# V2.net
KiCad netlist of a schematic drawn in EasyEDA Pro
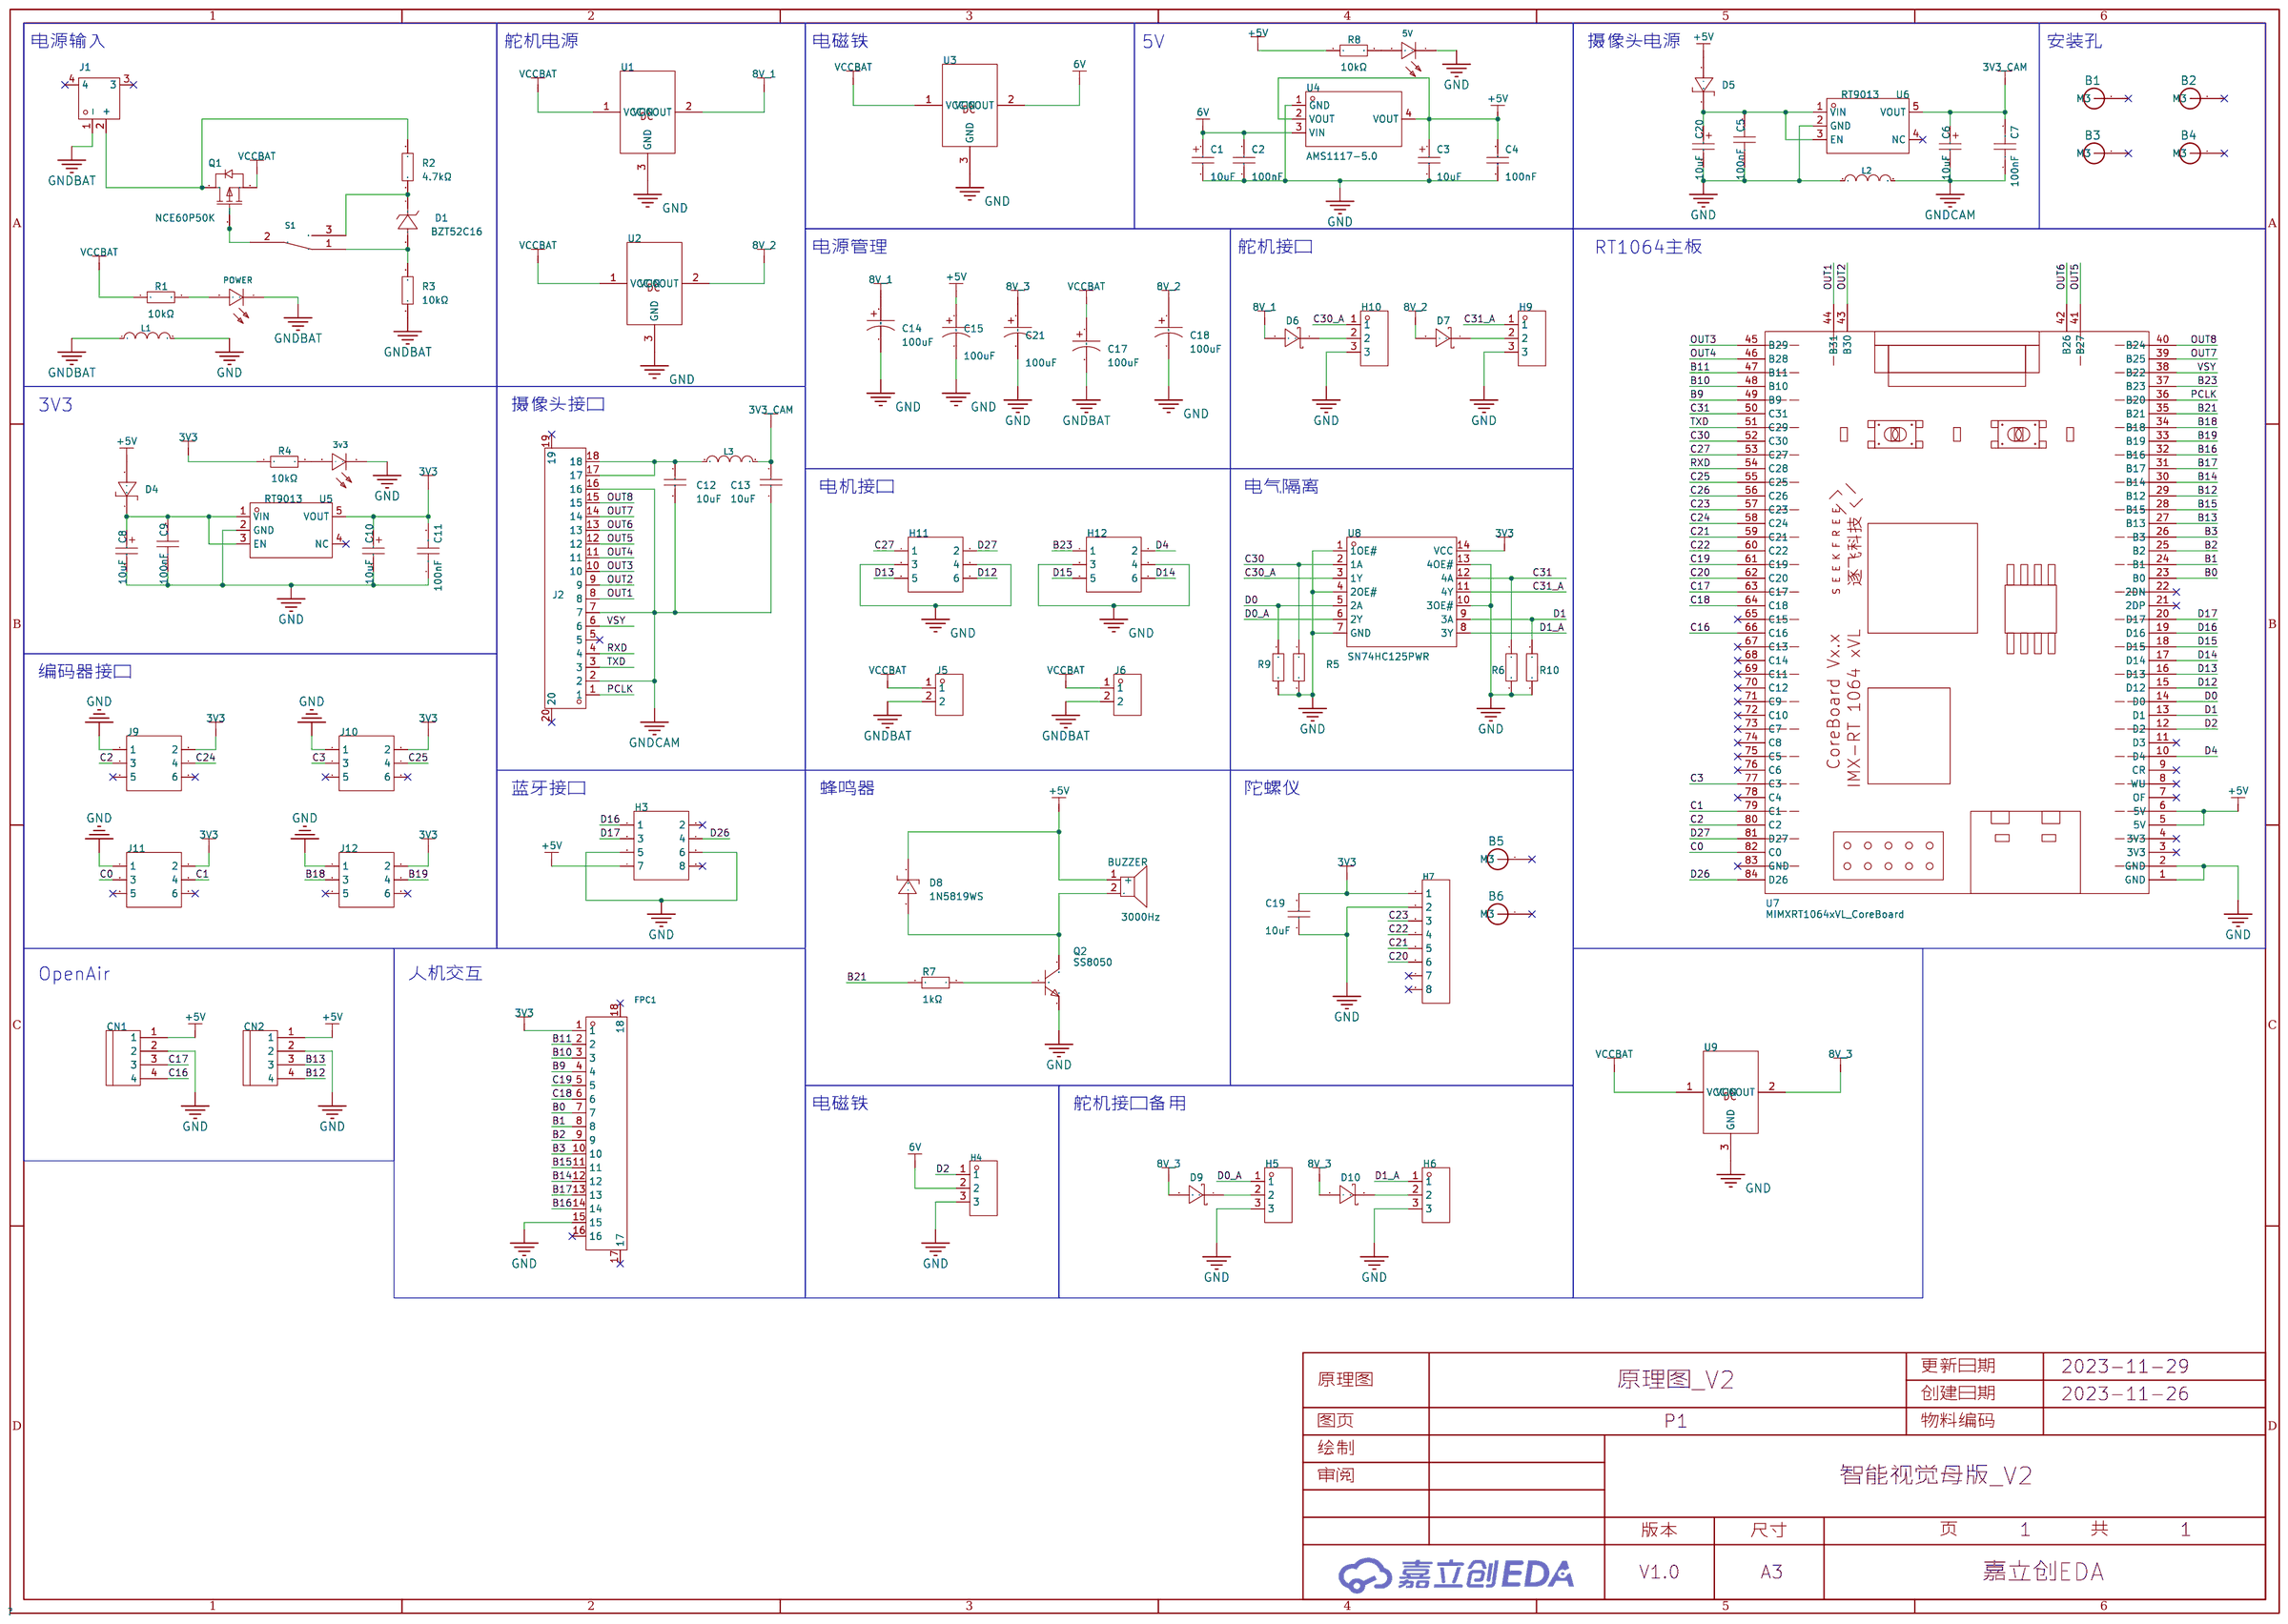
[diagram p0: schematic sheet]

(export (version "E")
  (design (tool "Eeschema 10.0.6"))
  (components
    (comp (ref "3v3")
      (value "NCD0603W1")
      (footprint "easyedapro:LED0603-RD")
      (description "发光颜色:白灯;")
      (fields (field (name "Manufacturer") "国星光电"))
      (libsource (lib "easyedapro") (part "FC-D1608WD-460H5"))
    )
    (comp (ref "5V")
      (value "NCD0603W1")
      (footprint "easyedapro:LED0603-RD")
      (description "发光颜色:白灯;")
      (fields (field (name "Manufacturer") "国星光电"))
      (libsource (lib "easyedapro") (part "FC-D1608WD-460H5"))
    )
    (comp (ref "B1")
      (value "M3螺柱孔_JX")
      (footprint "easyedapro:M3")
      (libsource (lib "easyedapro") (part "M3螺柱孔_JX"))
    )
    (comp (ref "B2")
      (value "M3螺柱孔_JX")
      (footprint "easyedapro:M3")
      (libsource (lib "easyedapro") (part "M3螺柱孔_JX"))
    )
    (comp (ref "B3")
      (value "M3螺柱孔_JX")
      (footprint "easyedapro:M3")
      (libsource (lib "easyedapro") (part "M3螺柱孔_JX"))
    )
    (comp (ref "B4")
      (value "M3螺柱孔_JX")
      (footprint "easyedapro:M3")
      (libsource (lib "easyedapro") (part "M3螺柱孔_JX"))
    )
    (comp (ref "B5")
      (value "M3螺柱孔_JX")
      (footprint "easyedapro:M3")
      (libsource (lib "easyedapro") (part "M3螺柱孔_JX"))
    )
    (comp (ref "B6")
      (value "M3螺柱孔_JX")
      (footprint "easyedapro:M3")
      (libsource (lib "easyedapro") (part "M3螺柱孔_JX"))
    )
    (comp (ref "BUZZER")
      (value "3000Hz")
      (footprint "easyedapro:BUZ-TH_BD9.6-P5.00-D0.7-FD")
      (description "驱动方式:有源(内含驱动线路);构造类型:电磁式;额定电压:5V;工作电压:4V~8V;频率:3000Hz;声压(SPL):85dB@5V,10cm;直径(φD):9mm;高度:5.7mm;")
      (fields (field (name "Manufacturer Part") "HNB09A05") (field (name "Manufacturer") "华能"))
      (libsource (lib "easyedapro") (part "HNB09A05"))
    )
    (comp (ref "C1")
      (value "10uF")
      (footprint "easyedapro:CAP-SMD_L3.2-W1.6-RD-C7171")
      (description "容值:10uF;精度:±10%;额定电压:16V;等效串联电阻:3Ω@100kHz;")
      (fields (field (name "Manufacturer Part") "TAJA106K016RNJ") (field (name "Manufacturer") "Kyocera AVX"))
      (libsource (lib "easyedapro") (part "TAJA106K016RNJ"))
    )
    (comp (ref "C2")
      (value "100nF")
      (footprint "easyedapro:C0603")
      (description "容值:100nF;精度:±10%;额定电压:50V;材质(温度系数):X7R;")
      (fields (field (name "Manufacturer Part") "0603B104K500NT") (field (name "Manufacturer") "FH(风华)"))
      (libsource (lib "easyedapro") (part "0603B104K500NT"))
    )
    (comp (ref "C3")
      (value "10uF")
      (footprint "easyedapro:CAP-SMD_L3.2-W1.6-RD-C7171")
      (description "容值:10uF;精度:±10%;额定电压:16V;等效串联电阻:3Ω@100kHz;")
      (fields (field (name "Manufacturer Part") "TAJA106K016RNJ") (field (name "Manufacturer") "Kyocera AVX"))
      (libsource (lib "easyedapro") (part "TAJA106K016RNJ"))
    )
    (comp (ref "C4")
      (value "100nF")
      (footprint "easyedapro:C0603")
      (description "容值:100nF;精度:±10%;额定电压:50V;材质(温度系数):X7R;")
      (fields (field (name "Manufacturer Part") "0603B104K500NT") (field (name "Manufacturer") "FH(风华)"))
      (libsource (lib "easyedapro") (part "0603B104K500NT"))
    )
    (comp (ref "C5")
      (value "100nF")
      (footprint "easyedapro:C0603")
      (libsource (lib "easyedapro") (part "C1210X7R475K630NT"))
    )
    (comp (ref "C6")
      (value "10uF")
      (footprint "easyedapro:CASE-A_3216")
      (description "容值:10uF;精度:±20%;额定电压:10V;等效串联电阻:8Ω@100kHz;工作温度:-55~+125;")
      (fields
        (field (name "Manufacturer Part") "CA45-A-10V-10uF-M")
        (field (name "Manufacturer") "CEC(振华新云)")
      )
      (libsource (lib "easyedapro") (part "CA45-A-10V-10UF-M"))
    )
    (comp (ref "C7")
      (value "100nF")
      (footprint "easyedapro:C0603")
      (libsource (lib "easyedapro") (part "C1210X7R475K630NT"))
    )
    (comp (ref "C8")
      (value "10uF")
      (footprint "easyedapro:CASE-A_3216")
      (description "容值:10uF;精度:±20%;额定电压:10V;等效串联电阻:8Ω@100kHz;工作温度:-55~+125;")
      (fields
        (field (name "Manufacturer Part") "CA45-A-10V-10uF-M")
        (field (name "Manufacturer") "CEC(振华新云)")
      )
      (libsource (lib "easyedapro") (part "CA45-A-10V-10UF-M"))
    )
    (comp (ref "C9")
      (value "100nF")
      (footprint "easyedapro:C0603")
      (libsource (lib "easyedapro") (part "C1210X7R475K630NT"))
    )
    (comp (ref "C10")
      (value "10uF")
      (footprint "easyedapro:CASE-A_3216")
      (description "容值:10uF;精度:±20%;额定电压:10V;等效串联电阻:8Ω@100kHz;工作温度:-55~+125;")
      (fields
        (field (name "Manufacturer Part") "CA45-A-10V-10uF-M")
        (field (name "Manufacturer") "CEC(振华新云)")
      )
      (libsource (lib "easyedapro") (part "CA45-A-10V-10UF-M"))
    )
    (comp (ref "C11")
      (value "100nF")
      (footprint "easyedapro:C0603")
      (libsource (lib "easyedapro") (part "C1210X7R475K630NT"))
    )
    (comp (ref "C12")
      (value "10uF")
      (footprint "easyedapro:C0805")
      (description "容值:10uF;精度:±10%;额定电压:25V;材质(温度系数):X5R;")
      (fields
        (field (name "Manufacturer Part") "CL21A106KAYNNNE")
        (field (name "Manufacturer") "SAMSUNG(三星)")
      )
      (libsource (lib "easyedapro") (part "CL21A106KAYNNNE"))
    )
    (comp (ref "C13")
      (value "10uF")
      (footprint "easyedapro:C0805")
      (description "容值:10uF;精度:±10%;额定电压:25V;材质(温度系数):X5R;")
      (fields
        (field (name "Manufacturer Part") "CL21A106KAYNNNE")
        (field (name "Manufacturer") "SAMSUNG(三星)")
      )
      (libsource (lib "easyedapro") (part "CL21A106KAYNNNE"))
    )
    (comp (ref "C14")
      (value "100uF")
      (footprint "easyedapro:CAP-TH_BD8.0-P3.50-D0.6-FD")
      (fields
        (field (name "Manufacturer Part") "25PZE220M8X9")
        (field (name "Manufacturer") "rubycon(红宝石)")
        (field (name "Tolerance") "±20%")
      )
      (libsource (lib "easyedapro") (part "25PZE220M8X9"))
    )
    (comp (ref "C15")
      (value "100uF")
      (footprint "easyedapro:CAP-TH_BD8.0-P3.50-D0.6-FD")
      (fields
        (field (name "Manufacturer Part") "25PZE220M8X9")
        (field (name "Manufacturer") "rubycon(红宝石)")
        (field (name "Tolerance") "±20%")
      )
      (libsource (lib "easyedapro") (part "25PZE220M8X9"))
    )
    (comp (ref "C17")
      (value "100uF")
      (footprint "easyedapro:CAP-TH_BD8.0-P3.50-D0.6-FD")
      (fields
        (field (name "Manufacturer Part") "25PZE220M8X9")
        (field (name "Manufacturer") "rubycon(红宝石)")
        (field (name "Tolerance") "±20%")
      )
      (libsource (lib "easyedapro") (part "25PZE220M8X9"))
    )
    (comp (ref "C18")
      (value "100uF")
      (footprint "easyedapro:CAP-TH_BD8.0-P3.50-D0.6-FD")
      (fields
        (field (name "Manufacturer Part") "25PZE220M8X9")
        (field (name "Manufacturer") "rubycon(红宝石)")
        (field (name "Tolerance") "±20%")
      )
      (libsource (lib "easyedapro") (part "25PZE220M8X9"))
    )
    (comp (ref "C19")
      (value "10uF")
      (footprint "easyedapro:C0805")
      (description "容值:10uF;精度:±10%;额定电压:25V;材质(温度系数):X5R;")
      (fields
        (field (name "Manufacturer Part") "CL21A106KAYNNNE")
        (field (name "Manufacturer") "SAMSUNG(三星)")
      )
      (libsource (lib "easyedapro") (part "CL21A106KAYNNNE"))
    )
    (comp (ref "C20")
      (value "10uF")
      (footprint "easyedapro:CASE-A_3216")
      (description "容值:10uF;精度:±20%;额定电压:10V;等效串联电阻:8Ω@100kHz;工作温度:-55~+125;")
      (fields
        (field (name "Manufacturer Part") "CA45-A-10V-10uF-M")
        (field (name "Manufacturer") "CEC(振华新云)")
      )
      (libsource (lib "easyedapro") (part "CA45-A-10V-10UF-M"))
    )
    (comp (ref "C21")
      (value "100uF")
      (footprint "easyedapro:CAP-TH_BD8.0-P3.50-D0.6-FD")
      (fields
        (field (name "Manufacturer Part") "25PZE220M8X9")
        (field (name "Manufacturer") "rubycon(红宝石)")
        (field (name "Tolerance") "±20%")
      )
      (libsource (lib "easyedapro") (part "25PZE220M8X9"))
    )
    (comp (ref "CN1")
      (value "XH-4AW")
      (footprint "easyedapro:CONN-TH_XH2.54-4AW")
      (description "参考系列:XH;间距:2.5mm;插针结构:1x4P;排数:1;每排PIN数:4;行距:-;安装方式:-;触头材质:磷青铜;")
      (fields (field (name "Manufacturer") "BOOMELE(博穆精密)"))
      (libsource (lib "easyedapro") (part "XH2.54-4AW"))
    )
    (comp (ref "CN2")
      (value "XH-4AW")
      (footprint "easyedapro:CONN-TH_XH2.54-4AW")
      (description "参考系列:XH;间距:2.5mm;插针结构:1x4P;排数:1;每排PIN数:4;行距:-;安装方式:-;触头材质:磷青铜;")
      (fields (field (name "Manufacturer") "BOOMELE(博穆精密)"))
      (libsource (lib "easyedapro") (part "XH2.54-4AW"))
    )
    (comp (ref "D1")
      (value "BZT52C16")
      (footprint "easyedapro:SOD-123_L2.7-W1.6-LS3.7-RD")
      (description "稳压值(标称值):-;精度:-;功率:500mW;反向电流(Ir):100nA@11.2V;")
      (fields (field (name "Manufacturer") "Slkor(萨科微)"))
      (libsource (lib "easyedapro") (part "BZT52C16_C707145"))
    )
    (comp (ref "D4")
      (value "1N5819WS")
      (footprint "easyedapro:SOD-323_L1.8-W1.3-LS2.5-RD")
      (description "直流反向耐压(Vr):40V;平均整流电流(Io):1A;正向压降(Vf):600mV@1A;")
      (fields (field (name "Manufacturer") "Hottech(合科泰)"))
      (libsource (lib "easyedapro") (part "1N5819WS"))
    )
    (comp (ref "D5")
      (value "1N5819WS")
      (footprint "easyedapro:SOD-323_L1.8-W1.3-LS2.5-RD")
      (description "直流反向耐压(Vr):40V;平均整流电流(Io):1A;正向压降(Vf):600mV@1A;")
      (fields (field (name "Manufacturer") "Hottech(合科泰)"))
      (libsource (lib "easyedapro") (part "1N5819WS"))
    )
    (comp (ref "D6")
      (value "1N5819W")
      (footprint "easyedapro:SOD-123_L2.8-W1.8-LS3.7-RD")
      (description "正向压降(Vf):600mV@1A;直流反向耐压(Vr):40V;平均整流电流(Io):1A;")
      (fields (field (name "Manufacturer") "KEXIN(科信)"))
      (libsource (lib "easyedapro") (part "1N5819W_C369930"))
    )
    (comp (ref "D7")
      (value "1N5819W")
      (footprint "easyedapro:SOD-123_L2.8-W1.8-LS3.7-RD")
      (description "正向压降(Vf):600mV@1A;直流反向耐压(Vr):40V;平均整流电流(Io):1A;")
      (fields (field (name "Manufacturer") "KEXIN(科信)"))
      (libsource (lib "easyedapro") (part "1N5819W_C369930"))
    )
    (comp (ref "D8")
      (value "1N5819WS")
      (footprint "easyedapro:SOD-323_L1.8-W1.3-LS2.5-RD")
      (description "直流反向耐压(Vr):40V;平均整流电流(Io):1A;正向压降(Vf):600mV@1A;")
      (fields (field (name "Manufacturer") "Hottech(合科泰)"))
      (libsource (lib "easyedapro") (part "1N5819WS"))
    )
    (comp (ref "D9")
      (value "1N5819W")
      (footprint "easyedapro:SOD-123_L2.8-W1.8-LS3.7-RD")
      (description "正向压降(Vf):600mV@1A;直流反向耐压(Vr):40V;平均整流电流(Io):1A;")
      (fields (field (name "Manufacturer") "KEXIN(科信)"))
      (libsource (lib "easyedapro") (part "1N5819W_C369930"))
    )
    (comp (ref "D10")
      (value "1N5819W")
      (footprint "easyedapro:SOD-123_L2.8-W1.8-LS3.7-RD")
      (description "正向压降(Vf):600mV@1A;直流反向耐压(Vr):40V;平均整流电流(Io):1A;")
      (fields (field (name "Manufacturer") "KEXIN(科信)"))
      (libsource (lib "easyedapro") (part "1N5819W_C369930"))
    )
    (comp (ref "FPC1")
      (value "FPC-05F-16PH20")
      (footprint "easyedapro:FPC-SMD_16P-P0.50_FPC-05F-16PH20")
      (description "间距:0.5mm;触点数量:16P;锁定特性:翻盖式;安装类型:卧贴;触点类型:下接;工作温度范围:-25°C~+85°C;")
      (fields (field (name "Manufacturer") "XUNPU(讯普)"))
      (libsource (lib "easyedapro") (part "FPC-05F-16PH20"))
    )
    (comp (ref "H3")
      (value "~")
      (footprint "easyedapro:HDR-TH_8P-P2.54-V-F-R2-C4-S2.54-1")
      (libsource (lib "easyedapro") (part "HDR-F-2.54_2x4"))
    )
    (comp (ref "H4")
      (value "~")
      (footprint "easyedapro:HDR-TH_3P-P2.54-V-F")
      (libsource (lib "easyedapro") (part "PM254V-11-03-H85"))
    )
    (comp (ref "H5")
      (value "~")
      (footprint "easyedapro:HDR-TH_3P-P2.54-V-M")
      (libsource (lib "easyedapro") (part "PZ254V-11-03P_C2937625"))
    )
    (comp (ref "H6")
      (value "~")
      (footprint "easyedapro:HDR-TH_3P-P2.54-V-M")
      (libsource (lib "easyedapro") (part "PZ254V-11-03P_C2937625"))
    )
    (comp (ref "H7")
      (value "~")
      (footprint "easyedapro:HDR-TH_8P-P2.54-V-F-1")
      (libsource (lib "easyedapro") (part "Header-Female-2.54_1x8"))
    )
    (comp (ref "H9")
      (value "~")
      (footprint "easyedapro:HDR-TH_3P-P2.54-V-M")
      (libsource (lib "easyedapro") (part "PZ254V-11-03P_C2937625"))
    )
    (comp (ref "H10")
      (value "~")
      (footprint "easyedapro:HDR-TH_3P-P2.54-V-M")
      (libsource (lib "easyedapro") (part "PZ254V-11-03P_C2937625"))
    )
    (comp (ref "H11")
      (value "~")
      (footprint "easyedapro:HDR-TH_6P-P2.54-V-R2-C3-S2.54_A2541WV-2X3P")
      (libsource (lib "easyedapro") (part "HDR-M-2.54_2x3"))
    )
    (comp (ref "H12")
      (value "~")
      (footprint "easyedapro:HDR-TH_6P-P2.54-V-R2-C3-S2.54_A2541WV-2X3P")
      (libsource (lib "easyedapro") (part "HDR-M-2.54_2x3"))
    )
    (comp (ref "J1")
      (value "XT60PW-M")
      (footprint "easyedapro:CONN-TH_XT60PW-M")
      (description "模型锂电连接器")
      (fields (field (name "Manufacturer") "AMASS(艾迈斯)"))
      (libsource (lib "easyedapro") (part "XT60PW-M"))
    )
    (comp (ref "J2")
      (value "J2")
      (footprint "easyedapro:FPC-SMD_18P-P0.50_FPC-05F-18PH20")
      (description "间距:0.5mm;触点数量:18P;锁定特性:翻盖式;安装类型:卧贴;触点类型:下接;工作温度范围:-25°C~+85°C;")
      (fields (field (name "Manufacturer") "XUNPU(讯普)"))
      (libsource (lib "easyedapro") (part "FPC-05F-18PH20"))
    )
    (comp (ref "J5")
      (value "KF301-5.0-2P")
      (footprint "easyedapro:CONN-TH_P5.00_KF301-5.0-2P")
      (fields (field (name "Manufacturer") "KEFA(科发)"))
      (libsource (lib "easyedapro") (part "KF301-5.0-2P"))
    )
    (comp (ref "J6")
      (value "KF301-5.0-2P")
      (footprint "easyedapro:CONN-TH_P5.00_KF301-5.0-2P")
      (fields (field (name "Manufacturer") "KEFA(科发)"))
      (libsource (lib "easyedapro") (part "KF301-5.0-2P"))
    )
    (comp (ref "J9")
      (value "~")
      (footprint "easyedapro:HDR-TH_6P-P2.54-V-R2-C3-S2.54_A2541WV-2X3P")
      (libsource (lib "easyedapro") (part "HDR-M-2.54_2x3"))
    )
    (comp (ref "J10")
      (value "~")
      (footprint "easyedapro:HDR-TH_6P-P2.54-V-R2-C3-S2.54_A2541WV-2X3P")
      (libsource (lib "easyedapro") (part "HDR-M-2.54_2x3"))
    )
    (comp (ref "J11")
      (value "~")
      (footprint "easyedapro:HDR-TH_6P-P2.54-V-R2-C3-S2.54_A2541WV-2X3P")
      (libsource (lib "easyedapro") (part "HDR-M-2.54_2x3"))
    )
    (comp (ref "J12")
      (value "~")
      (footprint "easyedapro:HDR-TH_6P-P2.54-V-R2-C3-S2.54_A2541WV-2X3P")
      (libsource (lib "easyedapro") (part "HDR-M-2.54_2x3"))
    )
    (comp (ref "L1")
      (value "CBG201209U000T")
      (footprint "easyedapro:L0805")
      (description "标称阻抗@测试频率:0Ω@100MHz;直流电阻(RDC):80mΩ;")
      (fields (field (name "Manufacturer") "FH(风华)"))
      (libsource (lib "easyedapro") (part "CBG201209U000T"))
    )
    (comp (ref "L2")
      (value "CBG201209U000T")
      (footprint "easyedapro:L0805")
      (description "标称阻抗@测试频率:0Ω@100MHz;直流电阻(RDC):80mΩ;")
      (fields (field (name "Manufacturer") "FH(风华)"))
      (libsource (lib "easyedapro") (part "CBG201209U000T"))
    )
    (comp (ref "L3")
      (value "CBG201209U000T")
      (footprint "easyedapro:L0805")
      (description "标称阻抗@测试频率:0Ω@100MHz;直流电阻(RDC):80mΩ;")
      (fields (field (name "Manufacturer") "FH(风华)"))
      (libsource (lib "easyedapro") (part "CBG201209U000T"))
    )
    (comp (ref "POWER")
      (value "NCD0603R1")
      (footprint "easyedapro:LED0603-RD_RED")
      (description "发光颜色:红灯;")
      (fields (field (name "Manufacturer") "国星光电"))
      (libsource (lib "easyedapro") (part "FC-DA1608HRK-620D"))
    )
    (comp (ref "Q1")
      (value "NCE60P50K")
      (footprint "easyedapro:TO-252-2_L6.6-W6.1-P4.57-LS9.9-TL-CW")
      (fields (field (name "Manufacturer") "NCE(无锡新洁能)"))
      (libsource (lib "easyedapro") (part "NCE60P50K"))
    )
    (comp (ref "Q2")
      (value "SS8050")
      (footprint "easyedapro:SOT-23-3_L2.9-W1.3-P1.90-LS2.4-BR")
      (description "晶体管类型:NPN;集射极击穿电压(Vceo):25V;集电极电流(Ic):1.5A;功率(Pd):300mW;直流电流增益(hFE@Ic,Vce):200@100mA,1V;")
      (fields (field (name "Manufacturer") "CJ(江苏长电/长晶)"))
      (libsource (lib "easyedapro") (part "SS8050_C2150"))
    )
    (comp (ref "R1")
      (value "10kΩ")
      (footprint "easyedapro:R0603")
      (description "电阻类型:厚膜电阻;阻值:10kΩ;精度:±1%;功率:100mW;")
      (fields
        (field (name "Manufacturer Part") "0603WAF1002T5E")
        (field (name "Manufacturer") "UNI-ROYAL(厚声)")
      )
      (libsource (lib "easyedapro") (part "0603WAF1002T5E"))
    )
    (comp (ref "R2")
      (value "4.7kΩ")
      (footprint "easyedapro:R0603")
      (description "电阻类型:厚膜电阻;阻值:4.7kΩ;精度:±1%;功率:100mW;")
      (fields
        (field (name "Manufacturer Part") "0603WAF4701T5E")
        (field (name "Manufacturer") "UNI-ROYAL(厚声)")
      )
      (libsource (lib "easyedapro") (part "0603WAF4701T5E"))
    )
    (comp (ref "R3")
      (value "10kΩ")
      (footprint "easyedapro:R0603")
      (description "电阻类型:厚膜电阻;阻值:10kΩ;精度:±1%;功率:100mW;")
      (fields
        (field (name "Manufacturer Part") "0603WAF1002T5E")
        (field (name "Manufacturer") "UNI-ROYAL(厚声)")
      )
      (libsource (lib "easyedapro") (part "0603WAF1002T5E"))
    )
    (comp (ref "R4")
      (value "10kΩ")
      (footprint "easyedapro:R0603")
      (description "电阻类型:厚膜电阻;阻值:10kΩ;精度:±1%;功率:100mW;")
      (fields
        (field (name "Manufacturer Part") "0603WAF1002T5E")
        (field (name "Manufacturer") "UNI-ROYAL(厚声)")
      )
      (libsource (lib "easyedapro") (part "0603WAF1002T5E"))
    )
    (comp (ref "R5")
      (value "10kΩ")
      (footprint "easyedapro:R0603")
      (description "电阻类型:厚膜电阻;阻值:10kΩ;精度:±1%;功率:100mW;")
      (fields
        (field (name "Manufacturer Part") "0603WAF1002T5E")
        (field (name "Manufacturer") "UNI-ROYAL(厚声)")
      )
      (libsource (lib "easyedapro") (part "0603WAF1002T5E"))
    )
    (comp (ref "R6")
      (value "10kΩ")
      (footprint "easyedapro:R0603")
      (description "电阻类型:厚膜电阻;阻值:10kΩ;精度:±1%;功率:100mW;")
      (fields
        (field (name "Manufacturer Part") "0603WAF1002T5E")
        (field (name "Manufacturer") "UNI-ROYAL(厚声)")
      )
      (libsource (lib "easyedapro") (part "0603WAF1002T5E"))
    )
    (comp (ref "R7")
      (value "1kΩ")
      (footprint "easyedapro:R0603")
      (description "电阻类型:厚膜电阻;阻值:1kΩ;精度:±1%;功率:100mW;")
      (fields
        (field (name "Manufacturer Part") "0603WAF1001T5E")
        (field (name "Manufacturer") "UNI-ROYAL(厚声)")
      )
      (libsource (lib "easyedapro") (part "0603WAF1001T5E"))
    )
    (comp (ref "R8")
      (value "10kΩ")
      (footprint "easyedapro:R0603")
      (description "电阻类型:厚膜电阻;阻值:10kΩ;精度:±1%;功率:100mW;")
      (fields
        (field (name "Manufacturer Part") "0603WAF1002T5E")
        (field (name "Manufacturer") "UNI-ROYAL(厚声)")
      )
      (libsource (lib "easyedapro") (part "0603WAF1002T5E"))
    )
    (comp (ref "R9")
      (value "10kΩ")
      (footprint "easyedapro:R0603")
      (description "电阻类型:厚膜电阻;阻值:10kΩ;精度:±1%;功率:100mW;")
      (fields
        (field (name "Manufacturer Part") "0603WAF1002T5E")
        (field (name "Manufacturer") "UNI-ROYAL(厚声)")
      )
      (libsource (lib "easyedapro") (part "0603WAF1002T5E"))
    )
    (comp (ref "R10")
      (value "10kΩ")
      (footprint "easyedapro:R0603")
      (description "电阻类型:厚膜电阻;阻值:10kΩ;精度:±1%;功率:100mW;")
      (fields
        (field (name "Manufacturer Part") "0603WAF1002T5E")
        (field (name "Manufacturer") "UNI-ROYAL(厚声)")
      )
      (libsource (lib "easyedapro") (part "0603WAF1002T5E"))
    )
    (comp (ref "S1")
      (value "MT-0-102-A101-M200-RS")
      (footprint "easyedapro:SW-TH_MT-0-103-A101-M200-RS")
      (description "额定电流:5A;额定电压(AC):125V;电路结构:单刀双掷;机械寿命:-;安装方式:直插;")
      (fields (field (name "Manufacturer") "YUEN FUNG(源丰)"))
      (libsource (lib "easyedapro") (part "MT-0-102-A101-M200-RS+PJ"))
    )
    (comp (ref "U1") (value "~") (libsource (lib "easyedapro") (part "DC_Board")))
    (comp (ref "U2") (value "~") (libsource (lib "easyedapro") (part "DC_Board")))
    (comp (ref "U3") (value "~") (libsource (lib "easyedapro") (part "DC_Board")))
    (comp (ref "U4")
      (value "AMS1117-5.0")
      (footprint "easyedapro:SOT-223_L6.5-W3.5-P2.30-LS7.0-BR")
      (description "输出类型:固定;最大输入电压:12V;输出电压:5V;输出电流:1A;电源纹波抑制比(PSRR):68dB@(120Hz);输出极性:正;")
      (fields (field (name "Manufacturer") "AMS"))
      (libsource (lib "easyedapro") (part "AMS1117-5.0"))
    )
    (comp (ref "U5")
      (value "RT9013")
      (footprint "easyedapro:SOT-23-5_L2.9-W1.6-P0.95-LS2.8-BR")
      (fields (field (name "Manufacturer Part") "RT9013-30GB") (field (name "Manufacturer") "RICHTEK(台湾立锜)"))
      (libsource (lib "easyedapro") (part "RT9013-30GB"))
    )
    (comp (ref "U6")
      (value "RT9013")
      (footprint "easyedapro:SOT-23-5_L2.9-W1.6-P0.95-LS2.8-BR")
      (fields (field (name "Manufacturer Part") "RT9013-30GB") (field (name "Manufacturer") "RICHTEK(台湾立锜)"))
      (libsource (lib "easyedapro") (part "RT9013-30GB"))
    )
    (comp (ref "U7")
      (value "MIMXRT1064xVL_CoreBoard")
      (footprint "easyedapro:MIMXRT1064xVL_CoreBoard - 3D")
      (libsource (lib "easyedapro") (part "MIMXRT1064xVL_CoreBoard"))
    )
    (comp (ref "U8")
      (value "SN74HC125PWR")
      (footprint "easyedapro:TSSOP-14_L5.0-W4.4-P0.65-LS6.5-BL")
      (description "类型:缓冲器，非反相;电源电压:2V~6V;输入类型:-;输出类型:三态;低电平输出电流(IOL):7.8mA;高电平输出电流(IOH):7.8mA;工作温度:-40°C~+85°C;")
      (fields (field (name "Manufacturer") "TI(德州仪器)"))
      (libsource (lib "easyedapro") (part "SN74HC125PWR"))
    )
    (comp (ref "U9") (value "~") (libsource (lib "easyedapro") (part "DC_Board")))
  )
  (nets
    (net (code "1") (name "+5V") (class "Default")
      (node (ref "BUZZER") (pin "1") (pinfunction "+_1") (pintype "input"))
      (node (ref "C15") (pin "1") (pinfunction "1_1") (pintype "input"))
      (node (ref "C3") (pin "1") (pinfunction "1_1") (pintype "input"))
      (node (ref "C4") (pin "2") (pinfunction "2_2") (pintype "input"))
      (node (ref "CN1") (pin "1") (pinfunction "1_1") (pintype "unspecified"))
      (node (ref "CN2") (pin "1") (pinfunction "1_1") (pintype "unspecified"))
      (node (ref "D4") (pin "2") (pinfunction "A_2") (pintype "input"))
      (node (ref "D5") (pin "2") (pinfunction "A_2") (pintype "input"))
      (node (ref "D8") (pin "1") (pinfunction "C_1") (pintype "input"))
      (node (ref "H3") (pin "7") (pinfunction "7_7") (pintype "input"))
      (node (ref "R8") (pin "1") (pinfunction "1_1") (pintype "input"))
      (node (ref "U4") (pin "2") (pinfunction "VOUT_2") (pintype "unspecified"))
      (node (ref "U4") (pin "4") (pinfunction "VOUT_4") (pintype "unspecified"))
      (node (ref "U7") (pin "5") (pinfunction "5V_5") (pintype "input"))
      (node (ref "U7") (pin "6") (pinfunction "5V_6") (pintype "input"))
    )
    (net (code "2") (name "/B0") (class "Default")
      (node (ref "FPC1") (pin "7") (pinfunction "7_7") (pintype "input"))
      (node (ref "U7") (pin "23") (pinfunction "B0_23") (pintype "input"))
    )
    (net (code "3") (name "/B1") (class "Default")
      (node (ref "FPC1") (pin "8") (pinfunction "8_8") (pintype "input"))
      (node (ref "U7") (pin "24") (pinfunction "B1_24") (pintype "input"))
    )
    (net (code "4") (name "/B2") (class "Default")
      (node (ref "FPC1") (pin "9") (pinfunction "9_9") (pintype "input"))
      (node (ref "U7") (pin "25") (pinfunction "B2_25") (pintype "input"))
    )
    (net (code "5") (name "/B3") (class "Default")
      (node (ref "FPC1") (pin "10") (pinfunction "10_10") (pintype "input"))
      (node (ref "U7") (pin "26") (pinfunction "B3_26") (pintype "input"))
    )
    (net (code "6") (name "/B9") (class "Default")
      (node (ref "FPC1") (pin "4") (pinfunction "4_4") (pintype "input"))
      (node (ref "U7") (pin "49") (pinfunction "B9_49") (pintype "input"))
    )
    (net (code "7") (name "/B10") (class "Default")
      (node (ref "FPC1") (pin "3") (pinfunction "3_3") (pintype "input"))
      (node (ref "U7") (pin "48") (pinfunction "B10_48") (pintype "input"))
    )
    (net (code "8") (name "/B11") (class "Default")
      (node (ref "FPC1") (pin "2") (pinfunction "2_2") (pintype "input"))
      (node (ref "U7") (pin "47") (pinfunction "B11_47") (pintype "input"))
    )
    (net (code "9") (name "/B12") (class "Default")
      (node (ref "CN2") (pin "4") (pinfunction "4_4") (pintype "unspecified"))
      (node (ref "U7") (pin "29") (pinfunction "B12_29") (pintype "input"))
    )
    (net (code "10") (name "/B13") (class "Default")
      (node (ref "CN2") (pin "3") (pinfunction "3_3") (pintype "unspecified"))
      (node (ref "U7") (pin "27") (pinfunction "B13_27") (pintype "input"))
    )
    (net (code "11") (name "/B14") (class "Default")
      (node (ref "FPC1") (pin "12") (pinfunction "12_12") (pintype "input"))
      (node (ref "U7") (pin "30") (pinfunction "B14_30") (pintype "input"))
    )
    (net (code "12") (name "/B15") (class "Default")
      (node (ref "FPC1") (pin "11") (pinfunction "11_11") (pintype "input"))
      (node (ref "U7") (pin "28") (pinfunction "B15_28") (pintype "input"))
    )
    (net (code "13") (name "/B16") (class "Default")
      (node (ref "FPC1") (pin "14") (pinfunction "14_14") (pintype "input"))
      (node (ref "U7") (pin "32") (pinfunction "B16_32") (pintype "input"))
    )
    (net (code "14") (name "/B17") (class "Default")
      (node (ref "FPC1") (pin "13") (pinfunction "13_13") (pintype "input"))
      (node (ref "U7") (pin "31") (pinfunction "B17_31") (pintype "input"))
    )
    (net (code "15") (name "/B18") (class "Default")
      (node (ref "J12") (pin "3") (pinfunction "3_3") (pintype "input"))
      (node (ref "U7") (pin "34") (pinfunction "B18_34") (pintype "input"))
    )
    (net (code "16") (name "/B19") (class "Default")
      (node (ref "J12") (pin "4") (pinfunction "4_4") (pintype "input"))
      (node (ref "U7") (pin "33") (pinfunction "B19_33") (pintype "input"))
    )
    (net (code "17") (name "/B21") (class "Default")
      (node (ref "R7") (pin "1") (pinfunction "1_1") (pintype "input"))
      (node (ref "U7") (pin "35") (pinfunction "B21_35") (pintype "input"))
    )
    (net (code "18") (name "/B23") (class "Default")
      (node (ref "H12") (pin "1") (pinfunction "1_1") (pintype "input"))
      (node (ref "U7") (pin "37") (pinfunction "B23_37") (pintype "input"))
    )
    (net (code "19") (name "/C0") (class "Default")
      (node (ref "J11") (pin "3") (pinfunction "3_3") (pintype "input"))
      (node (ref "U7") (pin "82") (pinfunction "C0_82") (pintype "input"))
    )
    (net (code "20") (name "/C1") (class "Default")
      (node (ref "J11") (pin "4") (pinfunction "4_4") (pintype "input"))
      (node (ref "U7") (pin "79") (pinfunction "C1_79") (pintype "input"))
    )
    (net (code "21") (name "/C2") (class "Default")
      (node (ref "J9") (pin "3") (pinfunction "3_3") (pintype "input"))
      (node (ref "U7") (pin "80") (pinfunction "C2_80") (pintype "input"))
    )
    (net (code "22") (name "/C3") (class "Default")
      (node (ref "J10") (pin "3") (pinfunction "3_3") (pintype "input"))
      (node (ref "U7") (pin "77") (pinfunction "C3_77") (pintype "input"))
    )
    (net (code "23") (name "/C16") (class "Default")
      (node (ref "CN1") (pin "4") (pinfunction "4_4") (pintype "unspecified"))
      (node (ref "U7") (pin "66") (pinfunction "C16_66") (pintype "input"))
    )
    (net (code "24") (name "/C17") (class "Default")
      (node (ref "CN1") (pin "3") (pinfunction "3_3") (pintype "unspecified"))
      (node (ref "U7") (pin "63") (pinfunction "C17_63") (pintype "input"))
    )
    (net (code "25") (name "/C18") (class "Default")
      (node (ref "FPC1") (pin "6") (pinfunction "6_6") (pintype "input"))
      (node (ref "U7") (pin "64") (pinfunction "C18_64") (pintype "input"))
    )
    (net (code "26") (name "/C19") (class "Default")
      (node (ref "FPC1") (pin "5") (pinfunction "5_5") (pintype "input"))
      (node (ref "U7") (pin "61") (pinfunction "C19_61") (pintype "input"))
    )
    (net (code "27") (name "/C20") (class "Default")
      (node (ref "H7") (pin "6") (pinfunction "6_6") (pintype "input"))
      (node (ref "U7") (pin "62") (pinfunction "C20_62") (pintype "input"))
    )
    (net (code "28") (name "/C21") (class "Default")
      (node (ref "H7") (pin "5") (pinfunction "5_5") (pintype "input"))
      (node (ref "U7") (pin "59") (pinfunction "C21_59") (pintype "input"))
    )
    (net (code "29") (name "/C22") (class "Default")
      (node (ref "H7") (pin "4") (pinfunction "4_4") (pintype "input"))
      (node (ref "U7") (pin "60") (pinfunction "C22_60") (pintype "input"))
    )
    (net (code "30") (name "/C23") (class "Default")
      (node (ref "H7") (pin "3") (pinfunction "3_3") (pintype "input"))
      (node (ref "U7") (pin "57") (pinfunction "C23_57") (pintype "input"))
    )
    (net (code "31") (name "/C24") (class "Default")
      (node (ref "J9") (pin "4") (pinfunction "4_4") (pintype "input"))
      (node (ref "U7") (pin "58") (pinfunction "C24_58") (pintype "input"))
    )
    (net (code "32") (name "/C25") (class "Default")
      (node (ref "J10") (pin "4") (pinfunction "4_4") (pintype "input"))
      (node (ref "U7") (pin "55") (pinfunction "C25_55") (pintype "input"))
    )
    (net (code "33") (name "/C26") (class "Default")
      (node (ref "U7") (pin "56") (pinfunction "C26_56") (pintype "input"))
    )
    (net (code "34") (name "/C27") (class "Default")
      (node (ref "H11") (pin "1") (pinfunction "1_1") (pintype "input"))
      (node (ref "U7") (pin "53") (pinfunction "C27_53") (pintype "input"))
    )
    (net (code "35") (name "/C30") (class "Default")
      (node (ref "R5") (pin "1") (pinfunction "1_1") (pintype "input"))
      (node (ref "U7") (pin "52") (pinfunction "C30_52") (pintype "input"))
      (node (ref "U8") (pin "2") (pinfunction "1A_2") (pintype "input"))
    )
    (net (code "36") (name "/C30_A") (class "Default")
      (node (ref "H10") (pin "1") (pinfunction "1_1") (pintype "input"))
      (node (ref "U8") (pin "3") (pinfunction "1Y_3") (pintype "input"))
    )
    (net (code "37") (name "/C31") (class "Default")
      (node (ref "R6") (pin "1") (pinfunction "1_1") (pintype "input"))
      (node (ref "U7") (pin "50") (pinfunction "C31_50") (pintype "input"))
      (node (ref "U8") (pin "12") (pinfunction "4A_12") (pintype "input"))
    )
    (net (code "38") (name "/C31_A") (class "Default")
      (node (ref "H9") (pin "1") (pinfunction "1_1") (pintype "input"))
      (node (ref "U8") (pin "11") (pinfunction "4Y_11") (pintype "input"))
    )
    (net (code "39") (name "/D0") (class "Default")
      (node (ref "R9") (pin "1") (pinfunction "1_1") (pintype "input"))
      (node (ref "U7") (pin "14") (pinfunction "D0_14") (pintype "input"))
      (node (ref "U8") (pin "5") (pinfunction "2A_5") (pintype "input"))
    )
    (net (code "40") (name "/D0_A") (class "Default")
      (node (ref "H5") (pin "1") (pinfunction "1_1") (pintype "input"))
      (node (ref "U8") (pin "6") (pinfunction "2Y_6") (pintype "input"))
    )
    (net (code "41") (name "/D1") (class "Default")
      (node (ref "R10") (pin "1") (pinfunction "1_1") (pintype "input"))
      (node (ref "U7") (pin "13") (pinfunction "D1_13") (pintype "input"))
      (node (ref "U8") (pin "9") (pinfunction "3A_9") (pintype "input"))
    )
    (net (code "42") (name "/D1_A") (class "Default")
      (node (ref "H6") (pin "1") (pinfunction "1_1") (pintype "input"))
      (node (ref "U8") (pin "8") (pinfunction "3Y_8") (pintype "input"))
    )
    (net (code "43") (name "/D2") (class "Default")
      (node (ref "H4") (pin "1") (pinfunction "1_1") (pintype "input"))
      (node (ref "U7") (pin "12") (pinfunction "D2_12") (pintype "input"))
    )
    (net (code "44") (name "/D4") (class "Default")
      (node (ref "H12") (pin "2") (pinfunction "2_2") (pintype "input"))
      (node (ref "U7") (pin "10") (pinfunction "D4_10") (pintype "input"))
    )
    (net (code "45") (name "/D12") (class "Default")
      (node (ref "H11") (pin "6") (pinfunction "6_6") (pintype "input"))
      (node (ref "U7") (pin "15") (pinfunction "D12_15") (pintype "input"))
    )
    (net (code "46") (name "/D13") (class "Default")
      (node (ref "H11") (pin "5") (pinfunction "5_5") (pintype "input"))
      (node (ref "U7") (pin "16") (pinfunction "D13_16") (pintype "input"))
    )
    (net (code "47") (name "/D14") (class "Default")
      (node (ref "H12") (pin "6") (pinfunction "6_6") (pintype "input"))
      (node (ref "U7") (pin "17") (pinfunction "D14_17") (pintype "input"))
    )
    (net (code "48") (name "/D15") (class "Default")
      (node (ref "H12") (pin "5") (pinfunction "5_5") (pintype "input"))
      (node (ref "U7") (pin "18") (pinfunction "D15_18") (pintype "input"))
    )
    (net (code "49") (name "/D16") (class "Default")
      (node (ref "H3") (pin "1") (pinfunction "1_1") (pintype "input"))
      (node (ref "U7") (pin "19") (pinfunction "D16_19") (pintype "input"))
    )
    (net (code "50") (name "/D17") (class "Default")
      (node (ref "H3") (pin "3") (pinfunction "3_3") (pintype "input"))
      (node (ref "U7") (pin "20") (pinfunction "D17_20") (pintype "input"))
    )
    (net (code "51") (name "/D26") (class "Default")
      (node (ref "H3") (pin "4") (pinfunction "4_4") (pintype "input"))
      (node (ref "U7") (pin "84") (pinfunction "D26_84") (pintype "input"))
    )
    (net (code "52") (name "/D27") (class "Default")
      (node (ref "H11") (pin "2") (pinfunction "2_2") (pintype "input"))
      (node (ref "U7") (pin "81") (pinfunction "D27_81") (pintype "input"))
    )
    (net (code "53") (name "/OUT1") (class "Default")
      (node (ref "J2") (pin "8") (pinfunction "8_8") (pintype "input"))
      (node (ref "U7") (pin "44") (pinfunction "B31_44") (pintype "input"))
    )
    (net (code "54") (name "/OUT2") (class "Default")
      (node (ref "J2") (pin "9") (pinfunction "9_9") (pintype "input"))
      (node (ref "U7") (pin "43") (pinfunction "B30_43") (pintype "input"))
    )
    (net (code "55") (name "/OUT3") (class "Default")
      (node (ref "J2") (pin "10") (pinfunction "10_10") (pintype "input"))
      (node (ref "U7") (pin "45") (pinfunction "B29_45") (pintype "input"))
    )
    (net (code "56") (name "/OUT4") (class "Default")
      (node (ref "J2") (pin "11") (pinfunction "11_11") (pintype "input"))
      (node (ref "U7") (pin "46") (pinfunction "B28_46") (pintype "input"))
    )
    (net (code "57") (name "/OUT5") (class "Default")
      (node (ref "J2") (pin "12") (pinfunction "12_12") (pintype "input"))
      (node (ref "U7") (pin "41") (pinfunction "B27_41") (pintype "input"))
    )
    (net (code "58") (name "/OUT6") (class "Default")
      (node (ref "J2") (pin "13") (pinfunction "13_13") (pintype "input"))
      (node (ref "U7") (pin "42") (pinfunction "B26_42") (pintype "input"))
    )
    (net (code "59") (name "/OUT7") (class "Default")
      (node (ref "J2") (pin "14") (pinfunction "14_14") (pintype "input"))
      (node (ref "U7") (pin "39") (pinfunction "B25_39") (pintype "input"))
    )
    (net (code "60") (name "/OUT8") (class "Default")
      (node (ref "J2") (pin "15") (pinfunction "15_15") (pintype "input"))
      (node (ref "U7") (pin "40") (pinfunction "B24_40") (pintype "input"))
    )
    (net (code "61") (name "/PCLK") (class "Default")
      (node (ref "J2") (pin "1") (pinfunction "1_1") (pintype "input"))
      (node (ref "U7") (pin "36") (pinfunction "B20_36") (pintype "input"))
    )
    (net (code "62") (name "/RXD") (class "Default")
      (node (ref "J2") (pin "4") (pinfunction "4_4") (pintype "input"))
      (node (ref "U7") (pin "54") (pinfunction "C28_54") (pintype "input"))
    )
    (net (code "63") (name "/TXD") (class "Default")
      (node (ref "J2") (pin "3") (pinfunction "3_3") (pintype "input"))
      (node (ref "U7") (pin "51") (pinfunction "C29_51") (pintype "input"))
    )
    (net (code "64") (name "/VSY") (class "Default")
      (node (ref "J2") (pin "6") (pinfunction "6_6") (pintype "input"))
      (node (ref "U7") (pin "38") (pinfunction "B22_38") (pintype "input"))
    )
    (net (code "65") (name "3V3") (class "Default")
      (node (ref "C10") (pin "1") (pinfunction "1_1") (pintype "input"))
      (node (ref "C11") (pin "2") (pinfunction "2_2") (pintype "input"))
      (node (ref "C19") (pin "2") (pinfunction "2_2") (pintype "input"))
      (node (ref "FPC1") (pin "1") (pinfunction "1_1") (pintype "input"))
      (node (ref "H7") (pin "1") (pinfunction "1_1") (pintype "input"))
      (node (ref "J10") (pin "2") (pinfunction "2_2") (pintype "input"))
      (node (ref "J11") (pin "2") (pinfunction "2_2") (pintype "input"))
      (node (ref "J12") (pin "2") (pinfunction "2_2") (pintype "input"))
      (node (ref "J9") (pin "2") (pinfunction "2_2") (pintype "input"))
      (node (ref "R4") (pin "1") (pinfunction "1_1") (pintype "input"))
      (node (ref "U5") (pin "5") (pinfunction "VOUT_5") (pintype "input"))
      (node (ref "U8") (pin "14") (pinfunction "VCC_14") (pintype "input"))
    )
    (net (code "66") (name "3V3_CAM") (class "Default")
      (node (ref "C13") (pin "2") (pinfunction "2_2") (pintype "input"))
      (node (ref "C6") (pin "1") (pinfunction "1_1") (pintype "input"))
      (node (ref "C7") (pin "2") (pinfunction "2_2") (pintype "input"))
      (node (ref "L3") (pin "2") (pinfunction "2_2") (pintype "input"))
      (node (ref "U6") (pin "5") (pinfunction "VOUT_5") (pintype "input"))
    )
    (net (code "67") (name "6V") (class "Default")
      (node (ref "C1") (pin "1") (pinfunction "1_1") (pintype "input"))
      (node (ref "C2") (pin "2") (pinfunction "2_2") (pintype "input"))
      (node (ref "H4") (pin "2") (pinfunction "2_2") (pintype "input"))
      (node (ref "U3") (pin "2") (pinfunction "VCCOUT_2") (pintype "input"))
      (node (ref "U4") (pin "3") (pinfunction "VIN_3") (pintype "unspecified"))
    )
    (net (code "68") (name "8V_1") (class "Default")
      (node (ref "C14") (pin "1") (pinfunction "1_1") (pintype "input"))
      (node (ref "D6") (pin "2") (pinfunction "A_2") (pintype "unspecified"))
      (node (ref "U1") (pin "2") (pinfunction "VCCOUT_2") (pintype "input"))
    )
    (net (code "69") (name "8V_2") (class "Default")
      (node (ref "C18") (pin "1") (pinfunction "1_1") (pintype "input"))
      (node (ref "D7") (pin "2") (pinfunction "A_2") (pintype "unspecified"))
      (node (ref "U2") (pin "2") (pinfunction "VCCOUT_2") (pintype "input"))
    )
    (net (code "70") (name "8V_3") (class "Default")
      (node (ref "C21") (pin "1") (pinfunction "1_1") (pintype "input"))
      (node (ref "D10") (pin "2") (pinfunction "A_2") (pintype "unspecified"))
      (node (ref "D9") (pin "2") (pinfunction "A_2") (pintype "unspecified"))
      (node (ref "U9") (pin "2") (pinfunction "VCCOUT_2") (pintype "input"))
    )
    (net (code "71") (name "GND") (class "Default")
      (node (ref "3v3") (pin "1") (pinfunction "-_1") (pintype "input"))
      (node (ref "5V") (pin "1") (pinfunction "-_1") (pintype "input"))
      (node (ref "C1") (pin "2") (pinfunction "2_2") (pintype "input"))
      (node (ref "C10") (pin "2") (pinfunction "2_2") (pintype "input"))
      (node (ref "C11") (pin "1") (pinfunction "1_1") (pintype "input"))
      (node (ref "C14") (pin "2") (pinfunction "2_2") (pintype "input"))
      (node (ref "C15") (pin "2") (pinfunction "2_2") (pintype "input"))
      (node (ref "C18") (pin "2") (pinfunction "2_2") (pintype "input"))
      (node (ref "C19") (pin "1") (pinfunction "1_1") (pintype "input"))
      (node (ref "C2") (pin "1") (pinfunction "1_1") (pintype "input"))
      (node (ref "C20") (pin "2") (pinfunction "2_2") (pintype "input"))
      (node (ref "C21") (pin "2") (pinfunction "2_2") (pintype "input"))
      (node (ref "C3") (pin "2") (pinfunction "2_2") (pintype "input"))
      (node (ref "C4") (pin "1") (pinfunction "1_1") (pintype "input"))
      (node (ref "C5") (pin "1") (pinfunction "1_1") (pintype "input"))
      (node (ref "C8") (pin "2") (pinfunction "2_2") (pintype "input"))
      (node (ref "C9") (pin "1") (pinfunction "1_1") (pintype "input"))
      (node (ref "CN1") (pin "2") (pinfunction "2_2") (pintype "unspecified"))
      (node (ref "CN2") (pin "2") (pinfunction "2_2") (pintype "unspecified"))
      (node (ref "FPC1") (pin "15") (pinfunction "15_15") (pintype "input"))
      (node (ref "H10") (pin "3") (pinfunction "3_3") (pintype "input"))
      (node (ref "H11") (pin "3") (pinfunction "3_3") (pintype "input"))
      (node (ref "H11") (pin "4") (pinfunction "4_4") (pintype "input"))
      (node (ref "H12") (pin "3") (pinfunction "3_3") (pintype "input"))
      (node (ref "H12") (pin "4") (pinfunction "4_4") (pintype "input"))
      (node (ref "H3") (pin "5") (pinfunction "5_5") (pintype "input"))
      (node (ref "H3") (pin "6") (pinfunction "6_6") (pintype "input"))
      (node (ref "H4") (pin "3") (pinfunction "3_3") (pintype "input"))
      (node (ref "H5") (pin "3") (pinfunction "3_3") (pintype "input"))
      (node (ref "H6") (pin "3") (pinfunction "3_3") (pintype "input"))
      (node (ref "H7") (pin "2") (pinfunction "2_2") (pintype "input"))
      (node (ref "H9") (pin "3") (pinfunction "3_3") (pintype "input"))
      (node (ref "J10") (pin "1") (pinfunction "1_1") (pintype "input"))
      (node (ref "J11") (pin "1") (pinfunction "1_1") (pintype "input"))
      (node (ref "J12") (pin "1") (pinfunction "1_1") (pintype "input"))
      (node (ref "J9") (pin "1") (pinfunction "1_1") (pintype "input"))
      (node (ref "L1") (pin "2") (pinfunction "2_2") (pintype "input"))
      (node (ref "L2") (pin "1") (pinfunction "1_1") (pintype "input"))
      (node (ref "Q2") (pin "2") (pinfunction "E_2") (pintype "input"))
      (node (ref "R10") (pin "2") (pinfunction "2_2") (pintype "input"))
      (node (ref "R5") (pin "2") (pinfunction "2_2") (pintype "input"))
      (node (ref "R6") (pin "2") (pinfunction "2_2") (pintype "input"))
      (node (ref "R9") (pin "2") (pinfunction "2_2") (pintype "input"))
      (node (ref "U1") (pin "3") (pinfunction "GND_3") (pintype "input"))
      (node (ref "U2") (pin "3") (pinfunction "GND_3") (pintype "input"))
      (node (ref "U3") (pin "3") (pinfunction "GND_3") (pintype "input"))
      (node (ref "U4") (pin "1") (pinfunction "GND_1") (pintype "unspecified"))
      (node (ref "U5") (pin "2") (pinfunction "GND_2") (pintype "input"))
      (node (ref "U6") (pin "2") (pinfunction "GND_2") (pintype "input"))
      (node (ref "U7") (pin "1") (pinfunction "GND_1") (pintype "input"))
      (node (ref "U7") (pin "2") (pinfunction "GND_2") (pintype "input"))
      (node (ref "U8") (pin "1") (pinfunction "1OE#_1") (pintype "input"))
      (node (ref "U8") (pin "10") (pinfunction "3OE#_10") (pintype "input"))
      (node (ref "U8") (pin "13") (pinfunction "4OE#_13") (pintype "input"))
      (node (ref "U8") (pin "4") (pinfunction "2OE#_4") (pintype "input"))
      (node (ref "U8") (pin "7") (pinfunction "GND_7") (pintype "input"))
      (node (ref "U9") (pin "3") (pinfunction "GND_3") (pintype "input"))
    )
    (net (code "72") (name "GNDBAT") (class "Default")
      (node (ref "C17") (pin "2") (pinfunction "2_2") (pintype "input"))
      (node (ref "J1") (pin "1") (pinfunction "-_1") (pintype "input"))
      (node (ref "J5") (pin "2") (pinfunction "2_2") (pintype "input"))
      (node (ref "J6") (pin "2") (pinfunction "2_2") (pintype "input"))
      (node (ref "L1") (pin "1") (pinfunction "1_1") (pintype "input"))
      (node (ref "POWER") (pin "1") (pinfunction "K_1") (pintype "input"))
      (node (ref "R3") (pin "2") (pinfunction "2_2") (pintype "input"))
    )
    (net (code "73") (name "GNDCAM") (class "Default")
      (node (ref "C12") (pin "1") (pinfunction "1_1") (pintype "input"))
      (node (ref "C13") (pin "1") (pinfunction "1_1") (pintype "input"))
      (node (ref "C6") (pin "2") (pinfunction "2_2") (pintype "input"))
      (node (ref "C7") (pin "1") (pinfunction "1_1") (pintype "input"))
      (node (ref "J2") (pin "16") (pinfunction "16_16") (pintype "input"))
      (node (ref "J2") (pin "2") (pinfunction "2_2") (pintype "input"))
      (node (ref "J2") (pin "7") (pinfunction "7_7") (pintype "input"))
      (node (ref "L2") (pin "2") (pinfunction "2_2") (pintype "input"))
    )
    (net (code "74") (name "Net-(3v3-+)") (class "Default")
      (node (ref "3v3") (pin "2") (pinfunction "+_2") (pintype "input"))
      (node (ref "R4") (pin "2") (pinfunction "2_2") (pintype "input"))
    )
    (net (code "75") (name "Net-(5V-+)") (class "Default")
      (node (ref "5V") (pin "2") (pinfunction "+_2") (pintype "input"))
      (node (ref "R8") (pin "2") (pinfunction "2_2") (pintype "input"))
    )
    (net (code "76") (name "Net-(C12-Pad2)") (class "Default")
      (node (ref "C12") (pin "2") (pinfunction "2_2") (pintype "input"))
      (node (ref "J2") (pin "17") (pinfunction "17_17") (pintype "input"))
      (node (ref "J2") (pin "18") (pinfunction "18_18") (pintype "input"))
      (node (ref "L3") (pin "1") (pinfunction "1_1") (pintype "input"))
    )
    (net (code "77") (name "Net-(D1-A)") (class "Default")
      (node (ref "D1") (pin "2") (pinfunction "A_2") (pintype "input"))
      (node (ref "R3") (pin "1") (pinfunction "1_1") (pintype "input"))
      (node (ref "S1") (pin "1") (pinfunction "1_1") (pintype "input"))
    )
    (net (code "78") (name "Net-(D1-K)") (class "Default")
      (node (ref "D1") (pin "1") (pinfunction "K_1") (pintype "input"))
      (node (ref "R2") (pin "1") (pinfunction "1_1") (pintype "input"))
      (node (ref "S1") (pin "3") (pinfunction "3_3") (pintype "input"))
    )
    (net (code "79") (name "Net-(D4-C)") (class "Default")
      (node (ref "C8") (pin "1") (pinfunction "1_1") (pintype "input"))
      (node (ref "C9") (pin "2") (pinfunction "2_2") (pintype "input"))
      (node (ref "D4") (pin "1") (pinfunction "C_1") (pintype "input"))
      (node (ref "U5") (pin "1") (pinfunction "VIN_1") (pintype "input"))
      (node (ref "U5") (pin "3") (pinfunction "EN_3") (pintype "input"))
    )
    (net (code "80") (name "Net-(D5-C)") (class "Default")
      (node (ref "C20") (pin "1") (pinfunction "1_1") (pintype "input"))
      (node (ref "C5") (pin "2") (pinfunction "2_2") (pintype "input"))
      (node (ref "D5") (pin "1") (pinfunction "C_1") (pintype "input"))
      (node (ref "U6") (pin "1") (pinfunction "VIN_1") (pintype "input"))
      (node (ref "U6") (pin "3") (pinfunction "EN_3") (pintype "input"))
    )
    (net (code "81") (name "Net-(D6-K)") (class "Default")
      (node (ref "D6") (pin "1") (pinfunction "K_1") (pintype "unspecified"))
      (node (ref "H10") (pin "2") (pinfunction "2_2") (pintype "input"))
    )
    (net (code "82") (name "Net-(D7-K)") (class "Default")
      (node (ref "D7") (pin "1") (pinfunction "K_1") (pintype "unspecified"))
      (node (ref "H9") (pin "2") (pinfunction "2_2") (pintype "input"))
    )
    (net (code "83") (name "Net-(D8-A)") (class "Default")
      (node (ref "BUZZER") (pin "2") (pinfunction "2_2") (pintype "input"))
      (node (ref "D8") (pin "2") (pinfunction "A_2") (pintype "input"))
      (node (ref "Q2") (pin "3") (pinfunction "C_3") (pintype "input"))
    )
    (net (code "84") (name "Net-(D9-K)") (class "Default")
      (node (ref "D9") (pin "1") (pinfunction "K_1") (pintype "unspecified"))
      (node (ref "H5") (pin "2") (pinfunction "2_2") (pintype "input"))
    )
    (net (code "85") (name "Net-(D10-K)") (class "Default")
      (node (ref "D10") (pin "1") (pinfunction "K_1") (pintype "unspecified"))
      (node (ref "H6") (pin "2") (pinfunction "2_2") (pintype "input"))
    )
    (net (code "86") (name "Net-(J1-+)") (class "Default")
      (node (ref "J1") (pin "2") (pinfunction "+_2") (pintype "input"))
      (node (ref "Q1") (pin "3") (pinfunction "S_3") (pintype "input"))
      (node (ref "R2") (pin "2") (pinfunction "2_2") (pintype "input"))
    )
    (net (code "87") (name "Net-(POWER-A)") (class "Default")
      (node (ref "POWER") (pin "2") (pinfunction "A_2") (pintype "input"))
      (node (ref "R1") (pin "2") (pinfunction "2_2") (pintype "input"))
    )
    (net (code "88") (name "Net-(Q1-G)") (class "Default")
      (node (ref "Q1") (pin "1") (pinfunction "G_1") (pintype "input"))
      (node (ref "S1") (pin "2") (pinfunction "2_2") (pintype "input"))
    )
    (net (code "89") (name "Net-(Q2-B)") (class "Default")
      (node (ref "Q2") (pin "1") (pinfunction "B_1") (pintype "input"))
      (node (ref "R7") (pin "2") (pinfunction "2_2") (pintype "input"))
    )
    (net (code "90") (name "VCCBAT") (class "Default")
      (node (ref "C17") (pin "1") (pinfunction "1_1") (pintype "input"))
      (node (ref "J5") (pin "1") (pinfunction "1_1") (pintype "input"))
      (node (ref "J6") (pin "1") (pinfunction "1_1") (pintype "input"))
      (node (ref "Q1") (pin "2") (pinfunction "D_2") (pintype "input"))
      (node (ref "R1") (pin "1") (pinfunction "1_1") (pintype "input"))
      (node (ref "U1") (pin "1") (pinfunction "VCCIN_1") (pintype "input"))
      (node (ref "U2") (pin "1") (pinfunction "VCCIN_1") (pintype "input"))
      (node (ref "U3") (pin "1") (pinfunction "VCCIN_1") (pintype "input"))
      (node (ref "U9") (pin "1") (pinfunction "VCCIN_1") (pintype "input"))
    )
    (net (code "91") (name "unconnected-(B1-M3-Pad1)") (class "Default")
      (node (ref "B1") (pin "1") (pinfunction "M3_1") (pintype "input+no_connect"))
    )
    (net (code "92") (name "unconnected-(B2-M3-Pad1)") (class "Default")
      (node (ref "B2") (pin "1") (pinfunction "M3_1") (pintype "input+no_connect"))
    )
    (net (code "93") (name "unconnected-(B3-M3-Pad1)") (class "Default")
      (node (ref "B3") (pin "1") (pinfunction "M3_1") (pintype "input+no_connect"))
    )
    (net (code "94") (name "unconnected-(B4-M3-Pad1)") (class "Default")
      (node (ref "B4") (pin "1") (pinfunction "M3_1") (pintype "input+no_connect"))
    )
    (net (code "95") (name "unconnected-(B5-M3-Pad1)") (class "Default")
      (node (ref "B5") (pin "1") (pinfunction "M3_1") (pintype "input+no_connect"))
    )
    (net (code "96") (name "unconnected-(B6-M3-Pad1)") (class "Default")
      (node (ref "B6") (pin "1") (pinfunction "M3_1") (pintype "input+no_connect"))
    )
    (net (code "97") (name "unconnected-(FPC1-Pad16)") (class "Default")
      (node (ref "FPC1") (pin "16") (pinfunction "16_16") (pintype "input+no_connect"))
    )
    (net (code "98") (name "unconnected-(FPC1-Pad17)") (class "Default")
      (node (ref "FPC1") (pin "17") (pinfunction "17_17") (pintype "input+no_connect"))
    )
    (net (code "99") (name "unconnected-(FPC1-Pad18)") (class "Default")
      (node (ref "FPC1") (pin "18") (pinfunction "18_18") (pintype "input+no_connect"))
    )
    (net (code "100") (name "unconnected-(H3-Pad2)") (class "Default")
      (node (ref "H3") (pin "2") (pinfunction "2_2") (pintype "input+no_connect"))
    )
    (net (code "101") (name "unconnected-(H3-Pad8)") (class "Default")
      (node (ref "H3") (pin "8") (pinfunction "8_8") (pintype "input+no_connect"))
    )
    (net (code "102") (name "unconnected-(H7-Pad7)") (class "Default")
      (node (ref "H7") (pin "7") (pinfunction "7_7") (pintype "input+no_connect"))
    )
    (net (code "103") (name "unconnected-(H7-Pad8)") (class "Default")
      (node (ref "H7") (pin "8") (pinfunction "8_8") (pintype "input+no_connect"))
    )
    (net (code "104") (name "unconnected-(J1-Pad3)") (class "Default")
      (node (ref "J1") (pin "3") (pinfunction "3_3") (pintype "input+no_connect"))
    )
    (net (code "105") (name "unconnected-(J1-Pad4)") (class "Default")
      (node (ref "J1") (pin "4") (pinfunction "4_4") (pintype "input+no_connect"))
    )
    (net (code "106") (name "unconnected-(J2-Pad5)") (class "Default")
      (node (ref "J2") (pin "5") (pinfunction "5_5") (pintype "input+no_connect"))
    )
    (net (code "107") (name "unconnected-(J2-Pad19)") (class "Default")
      (node (ref "J2") (pin "19") (pinfunction "19_19") (pintype "input+no_connect"))
    )
    (net (code "108") (name "unconnected-(J2-Pad20)") (class "Default")
      (node (ref "J2") (pin "20") (pinfunction "20_20") (pintype "input+no_connect"))
    )
    (net (code "109") (name "unconnected-(J9-Pad5)") (class "Default")
      (node (ref "J9") (pin "5") (pinfunction "5_5") (pintype "input+no_connect"))
    )
    (net (code "110") (name "unconnected-(J9-Pad6)") (class "Default")
      (node (ref "J9") (pin "6") (pinfunction "6_6") (pintype "input+no_connect"))
    )
    (net (code "111") (name "unconnected-(J10-Pad5)") (class "Default")
      (node (ref "J10") (pin "5") (pinfunction "5_5") (pintype "input+no_connect"))
    )
    (net (code "112") (name "unconnected-(J10-Pad6)") (class "Default")
      (node (ref "J10") (pin "6") (pinfunction "6_6") (pintype "input+no_connect"))
    )
    (net (code "113") (name "unconnected-(J11-Pad5)") (class "Default")
      (node (ref "J11") (pin "5") (pinfunction "5_5") (pintype "input+no_connect"))
    )
    (net (code "114") (name "unconnected-(J11-Pad6)") (class "Default")
      (node (ref "J11") (pin "6") (pinfunction "6_6") (pintype "input+no_connect"))
    )
    (net (code "115") (name "unconnected-(J12-Pad5)") (class "Default")
      (node (ref "J12") (pin "5") (pinfunction "5_5") (pintype "input+no_connect"))
    )
    (net (code "116") (name "unconnected-(J12-Pad6)") (class "Default")
      (node (ref "J12") (pin "6") (pinfunction "6_6") (pintype "input+no_connect"))
    )
    (net (code "117") (name "unconnected-(U5-NC-Pad4)") (class "Default")
      (node (ref "U5") (pin "4") (pinfunction "NC_4") (pintype "input+no_connect"))
    )
    (net (code "118") (name "unconnected-(U6-NC-Pad4)") (class "Default")
      (node (ref "U6") (pin "4") (pinfunction "NC_4") (pintype "input+no_connect"))
    )
    (net (code "119") (name "unconnected-(U7-2DN-Pad22)") (class "Default")
      (node (ref "U7") (pin "22") (pinfunction "2DN_22") (pintype "input+no_connect"))
    )
    (net (code "120") (name "unconnected-(U7-2DP-Pad21)") (class "Default")
      (node (ref "U7") (pin "21") (pinfunction "2DP_21") (pintype "input+no_connect"))
    )
    (net (code "121") (name "unconnected-(U7-3V3-Pad3)") (class "Default")
      (node (ref "U7") (pin "3") (pinfunction "3V3_3") (pintype "input+no_connect"))
    )
    (net (code "122") (name "unconnected-(U7-3V3-Pad4)") (class "Default")
      (node (ref "U7") (pin "4") (pinfunction "3V3_4") (pintype "input+no_connect"))
    )
    (net (code "123") (name "unconnected-(U7-C4-Pad78)") (class "Default")
      (node (ref "U7") (pin "78") (pinfunction "C4_78") (pintype "input+no_connect"))
    )
    (net (code "124") (name "unconnected-(U7-C5-Pad75)") (class "Default")
      (node (ref "U7") (pin "75") (pinfunction "C5_75") (pintype "input+no_connect"))
    )
    (net (code "125") (name "unconnected-(U7-C6-Pad76)") (class "Default")
      (node (ref "U7") (pin "76") (pinfunction "C6_76") (pintype "input+no_connect"))
    )
    (net (code "126") (name "unconnected-(U7-C7-Pad73)") (class "Default")
      (node (ref "U7") (pin "73") (pinfunction "C7_73") (pintype "input+no_connect"))
    )
    (net (code "127") (name "unconnected-(U7-C8-Pad74)") (class "Default")
      (node (ref "U7") (pin "74") (pinfunction "C8_74") (pintype "input+no_connect"))
    )
    (net (code "128") (name "unconnected-(U7-C9-Pad71)") (class "Default")
      (node (ref "U7") (pin "71") (pinfunction "C9_71") (pintype "input+no_connect"))
    )
    (net (code "129") (name "unconnected-(U7-C10-Pad72)") (class "Default")
      (node (ref "U7") (pin "72") (pinfunction "C10_72") (pintype "input+no_connect"))
    )
    (net (code "130") (name "unconnected-(U7-C11-Pad69)") (class "Default")
      (node (ref "U7") (pin "69") (pinfunction "C11_69") (pintype "input+no_connect"))
    )
    (net (code "131") (name "unconnected-(U7-C12-Pad70)") (class "Default")
      (node (ref "U7") (pin "70") (pinfunction "C12_70") (pintype "input+no_connect"))
    )
    (net (code "132") (name "unconnected-(U7-C13-Pad67)") (class "Default")
      (node (ref "U7") (pin "67") (pinfunction "C13_67") (pintype "input+no_connect"))
    )
    (net (code "133") (name "unconnected-(U7-C14-Pad68)") (class "Default")
      (node (ref "U7") (pin "68") (pinfunction "C14_68") (pintype "input+no_connect"))
    )
    (net (code "134") (name "unconnected-(U7-C15-Pad65)") (class "Default")
      (node (ref "U7") (pin "65") (pinfunction "C15_65") (pintype "input+no_connect"))
    )
    (net (code "135") (name "unconnected-(U7-CR-Pad9)") (class "Default")
      (node (ref "U7") (pin "9") (pinfunction "CR_9") (pintype "input+no_connect"))
    )
    (net (code "136") (name "unconnected-(U7-D3-Pad11)") (class "Default")
      (node (ref "U7") (pin "11") (pinfunction "D3_11") (pintype "input+no_connect"))
    )
    (net (code "137") (name "unconnected-(U7-GND-Pad83)") (class "Default")
      (node (ref "U7") (pin "83") (pinfunction "GND_83") (pintype "input+no_connect"))
    )
    (net (code "138") (name "unconnected-(U7-OF-Pad7)") (class "Default")
      (node (ref "U7") (pin "7") (pinfunction "OF_7") (pintype "input+no_connect"))
    )
    (net (code "139") (name "unconnected-(U7-WU-Pad8)") (class "Default")
      (node (ref "U7") (pin "8") (pinfunction "WU_8") (pintype "input+no_connect"))
    )
  )
)
